# Serial-Enabled-LCD-Kit-v11.net
KiCad netlist of a schematic drawn in EAGLE
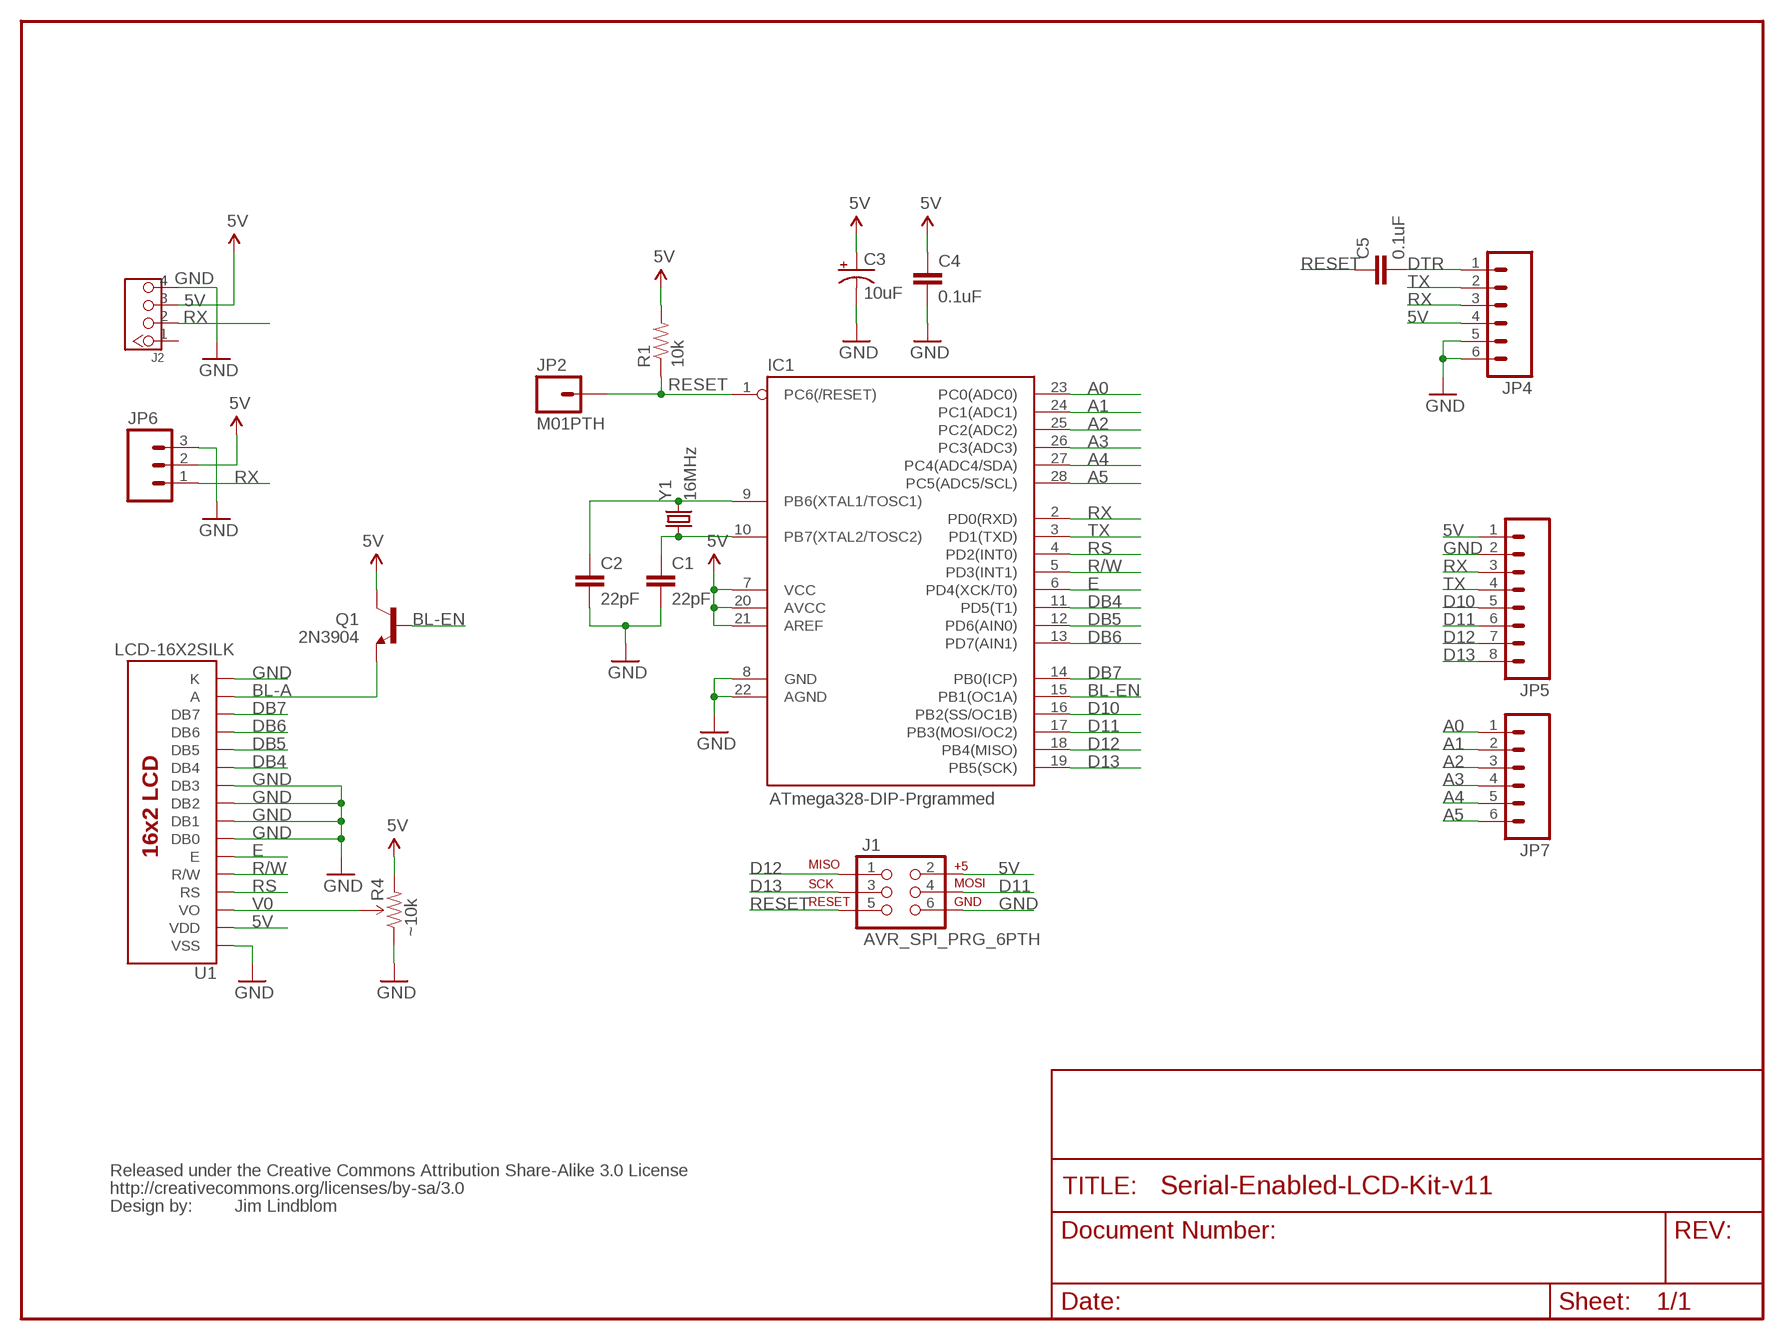
[diagram p0: schematic, sheet 1]

(export (version "E")
  (design (tool "Eeschema 10.0.6"))
  (components
    (comp (ref "C1")
      (value "22pF")
      (footprint "eagle-import:CAP-PTH-SMALL2")
      (libsource (lib "eagle-import") (part "CAPPTH2"))
    )
    (comp (ref "C2")
      (value "22pF")
      (footprint "eagle-import:CAP-PTH-SMALL2")
      (libsource (lib "eagle-import") (part "CAPPTH2"))
    )
    (comp (ref "C3")
      (value "10uF")
      (footprint "eagle-import:CPOL-RADIAL-10UF-25V")
      (libsource (lib "eagle-import") (part "CAP_POLPTH2"))
    )
    (comp (ref "C4")
      (value "0.1uF")
      (footprint "eagle-import:CAP-PTH-SMALL2")
      (libsource (lib "eagle-import") (part "CAPPTH2"))
    )
    (comp (ref "C5")
      (value "0.1uF")
      (footprint "eagle-import:CAP-PTH-SMALL2")
      (libsource (lib "eagle-import") (part "CAPPTH2"))
    )
    (comp (ref "IC1")
      (value "ATmega328-DIP-Prgrammed")
      (footprint "eagle-import:DIL28-3")
      (libsource (lib "eagle-import") (part "AVR-MEGA8-PPTH"))
    )
    (comp (ref "J1")
      (value "AVR_SPI_PRG_6PTH")
      (footprint "eagle-import:2X3")
      (libsource (lib "eagle-import") (part "AVR_SPI_PRG_6PTH"))
    )
    (comp (ref "J2")
      (value "TWIG-4P-2.0'90D'")
      (footprint "eagle-import:4P-2.0-90D")
      (libsource (lib "eagle-import") (part "TWIG-4P-2.0'90D'"))
    )
    (comp (ref "JP2")
      (value "M01PTH")
      (footprint "eagle-import:1X01")
      (libsource (lib "eagle-import") (part "M01PTH"))
    )
    (comp (ref "JP4")
      (value "M06SIP")
      (footprint "eagle-import:1X06")
      (libsource (lib "eagle-import") (part "M06SIP"))
    )
    (comp (ref "JP5")
      (value "M08")
      (footprint "eagle-import:1X08")
      (libsource (lib "eagle-import") (part "M08"))
    )
    (comp (ref "JP6")
      (value "M03PTH")
      (footprint "eagle-import:1X03")
      (libsource (lib "eagle-import") (part "M03PTH"))
    )
    (comp (ref "JP7")
      (value "M06SIP")
      (footprint "eagle-import:1X06")
      (libsource (lib "eagle-import") (part "M06SIP"))
    )
    (comp (ref "Q1")
      (value "2N3904")
      (footprint "eagle-import:TO-92")
      (libsource (lib "eagle-import") (part "TRANSISTOR_NPNTO92"))
    )
    (comp (ref "R1")
      (value "10k")
      (footprint "eagle-import:AXIAL-0.3")
      (libsource (lib "eagle-import") (part "RESISTORAXIAL-0.3"))
    )
    (comp (ref "R4")
      (value "~10k")
      (footprint "eagle-import:TRIM_POT_PTH")
      (libsource (lib "eagle-import") (part "TRIMPOTPTH"))
    )
    (comp (ref "U$4")
      (value "CREATIVE_COMMONS")
      (footprint "eagle-import:CREATIVE_COMMONS")
      (libsource (lib "eagle-import") (part "CREATIVE_COMMONS"))
    )
    (comp (ref "U1")
      (value "LCD-16X2SILK")
      (footprint "eagle-import:LCD-16X2")
      (libsource (lib "eagle-import") (part "LCD-16X2SILK"))
    )
    (comp (ref "Y1")
      (value "16MHz")
      (footprint "eagle-import:HC49US")
      (libsource (lib "eagle-import") (part "CRYSTALHC49US"))
    )
  )
  (nets
    (net (code "1") (name "/A0") (class "Default")
      (node (ref "IC1") (pin "23") (pinfunction "PC0(ADC0)_23") (pintype "bidirectional"))
      (node (ref "JP7") (pin "1") (pinfunction "1_1") (pintype "passive"))
    )
    (net (code "2") (name "/A1") (class "Default")
      (node (ref "IC1") (pin "24") (pinfunction "PC1(ADC1)_24") (pintype "bidirectional"))
      (node (ref "JP7") (pin "2") (pinfunction "2_2") (pintype "passive"))
    )
    (net (code "3") (name "/A2") (class "Default")
      (node (ref "IC1") (pin "25") (pinfunction "PC2(ADC2)_25") (pintype "bidirectional"))
      (node (ref "JP7") (pin "3") (pinfunction "3_3") (pintype "passive"))
    )
    (net (code "4") (name "/A3") (class "Default")
      (node (ref "IC1") (pin "26") (pinfunction "PC3(ADC3)_26") (pintype "bidirectional"))
      (node (ref "JP7") (pin "4") (pinfunction "4_4") (pintype "passive"))
    )
    (net (code "5") (name "/A4") (class "Default")
      (node (ref "IC1") (pin "27") (pinfunction "PC4(ADC4/SDA)_27") (pintype "bidirectional"))
      (node (ref "JP7") (pin "5") (pinfunction "5_5") (pintype "passive"))
    )
    (net (code "6") (name "/A5") (class "Default")
      (node (ref "IC1") (pin "28") (pinfunction "PC5(ADC5/SCL)_28") (pintype "bidirectional"))
      (node (ref "JP7") (pin "6") (pinfunction "6_6") (pintype "passive"))
    )
    (net (code "7") (name "/BL-A") (class "Default")
      (node (ref "Q1") (pin "1") (pinfunction "E_1") (pintype "passive"))
      (node (ref "U1") (pin "15") (pinfunction "A_15") (pintype "power_in"))
    )
    (net (code "8") (name "/BL-EN") (class "Default")
      (node (ref "IC1") (pin "15") (pinfunction "PB1(OC1A)_15") (pintype "bidirectional"))
      (node (ref "Q1") (pin "2") (pinfunction "B_2") (pintype "passive"))
    )
    (net (code "9") (name "/D10") (class "Default")
      (node (ref "IC1") (pin "16") (pinfunction "PB2(SS/OC1B)_16") (pintype "bidirectional"))
      (node (ref "JP5") (pin "5") (pinfunction "5_5") (pintype "passive"))
    )
    (net (code "10") (name "/D11") (class "Default")
      (node (ref "IC1") (pin "17") (pinfunction "PB3(MOSI/OC2)_17") (pintype "bidirectional"))
      (node (ref "J1") (pin "4") (pinfunction "4_4") (pintype "passive"))
      (node (ref "JP5") (pin "6") (pinfunction "6_6") (pintype "passive"))
    )
    (net (code "11") (name "/D12") (class "Default")
      (node (ref "IC1") (pin "18") (pinfunction "PB4(MISO)_18") (pintype "bidirectional"))
      (node (ref "J1") (pin "1") (pinfunction "1_1") (pintype "passive"))
      (node (ref "JP5") (pin "7") (pinfunction "7_7") (pintype "passive"))
    )
    (net (code "12") (name "/D13") (class "Default")
      (node (ref "IC1") (pin "19") (pinfunction "PB5(SCK)_19") (pintype "bidirectional"))
      (node (ref "J1") (pin "3") (pinfunction "3_3") (pintype "passive"))
      (node (ref "JP5") (pin "8") (pinfunction "8_8") (pintype "passive"))
    )
    (net (code "13") (name "/DB4") (class "Default")
      (node (ref "IC1") (pin "11") (pinfunction "PD5(T1)_11") (pintype "bidirectional"))
      (node (ref "U1") (pin "11") (pinfunction "DB4_11") (pintype "bidirectional"))
    )
    (net (code "14") (name "/DB5") (class "Default")
      (node (ref "IC1") (pin "12") (pinfunction "PD6(AIN0)_12") (pintype "bidirectional"))
      (node (ref "U1") (pin "12") (pinfunction "DB5_12") (pintype "bidirectional"))
    )
    (net (code "15") (name "/DB6") (class "Default")
      (node (ref "IC1") (pin "13") (pinfunction "PD7(AIN1)_13") (pintype "bidirectional"))
      (node (ref "U1") (pin "13") (pinfunction "DB6_13") (pintype "bidirectional"))
    )
    (net (code "16") (name "/DB7") (class "Default")
      (node (ref "IC1") (pin "14") (pinfunction "PB0(ICP)_14") (pintype "bidirectional"))
      (node (ref "U1") (pin "14") (pinfunction "DB7_14") (pintype "bidirectional"))
    )
    (net (code "17") (name "/DTR") (class "Default")
      (node (ref "C5") (pin "2") (pinfunction "2_2") (pintype "passive"))
      (node (ref "JP4") (pin "1") (pinfunction "1_1") (pintype "passive"))
    )
    (net (code "18") (name "/E") (class "Default")
      (node (ref "IC1") (pin "6") (pinfunction "PD4(XCK/T0)_6") (pintype "bidirectional"))
      (node (ref "U1") (pin "6") (pinfunction "E_6") (pintype "input"))
    )
    (net (code "19") (name "/RESET") (class "Default")
      (node (ref "C5") (pin "1") (pinfunction "1_1") (pintype "passive"))
      (node (ref "IC1") (pin "1") (pinfunction "PC6(/RESET)_1") (pintype "bidirectional"))
      (node (ref "J1") (pin "5") (pinfunction "5_5") (pintype "passive"))
      (node (ref "JP2") (pin "1") (pinfunction "1_1") (pintype "passive"))
      (node (ref "R1") (pin "P$1") (pinfunction "1_P$1") (pintype "passive"))
    )
    (net (code "20") (name "/RS") (class "Default")
      (node (ref "IC1") (pin "4") (pinfunction "PD2(INT0)_4") (pintype "bidirectional"))
      (node (ref "U1") (pin "4") (pinfunction "RS_4") (pintype "input"))
    )
    (net (code "21") (name "/RX") (class "Default")
      (node (ref "IC1") (pin "2") (pinfunction "PD0(RXD)_2") (pintype "bidirectional"))
      (node (ref "J2") (pin "2") (pinfunction "2_2") (pintype "bidirectional"))
      (node (ref "JP4") (pin "3") (pinfunction "3_3") (pintype "passive"))
      (node (ref "JP5") (pin "3") (pinfunction "3_3") (pintype "passive"))
      (node (ref "JP6") (pin "1") (pinfunction "1_1") (pintype "passive"))
    )
    (net (code "22") (name "/R{slash}W") (class "Default")
      (node (ref "IC1") (pin "5") (pinfunction "PD3(INT1)_5") (pintype "bidirectional"))
      (node (ref "U1") (pin "5") (pinfunction "R/W_5") (pintype "input"))
    )
    (net (code "23") (name "/TX") (class "Default")
      (node (ref "IC1") (pin "3") (pinfunction "PD1(TXD)_3") (pintype "bidirectional"))
      (node (ref "JP4") (pin "2") (pinfunction "2_2") (pintype "passive"))
      (node (ref "JP5") (pin "4") (pinfunction "4_4") (pintype "passive"))
    )
    (net (code "24") (name "/V0") (class "Default")
      (node (ref "R4") (pin "2") (pinfunction "WIPER_2") (pintype "passive"))
      (node (ref "U1") (pin "3") (pinfunction "VO_3") (pintype "bidirectional"))
    )
    (net (code "25") (name "5V") (class "Default")
      (node (ref "C3") (pin "1") (pinfunction "+_1") (pintype "passive"))
      (node (ref "C4") (pin "1") (pinfunction "1_1") (pintype "passive"))
      (node (ref "IC1") (pin "20") (pinfunction "AVCC_20") (pintype "bidirectional"))
      (node (ref "IC1") (pin "21") (pinfunction "AREF_21") (pintype "bidirectional"))
      (node (ref "IC1") (pin "7") (pinfunction "VCC_7") (pintype "bidirectional"))
      (node (ref "J1") (pin "2") (pinfunction "2_2") (pintype "passive"))
      (node (ref "J2") (pin "3") (pinfunction "3_3") (pintype "bidirectional"))
      (node (ref "JP4") (pin "4") (pinfunction "4_4") (pintype "passive"))
      (node (ref "JP5") (pin "1") (pinfunction "1_1") (pintype "passive"))
      (node (ref "JP6") (pin "2") (pinfunction "2_2") (pintype "passive"))
      (node (ref "Q1") (pin "3") (pinfunction "C_3") (pintype "passive"))
      (node (ref "R1") (pin "P$2") (pinfunction "2_P$2") (pintype "passive"))
      (node (ref "R4") (pin "3") (pinfunction "CW_3") (pintype "passive"))
      (node (ref "U1") (pin "2") (pinfunction "VDD_2") (pintype "power_in"))
    )
    (net (code "26") (name "GND") (class "Default")
      (node (ref "C1") (pin "2") (pinfunction "2_2") (pintype "passive"))
      (node (ref "C2") (pin "2") (pinfunction "2_2") (pintype "passive"))
      (node (ref "C3") (pin "2") (pinfunction "-_2") (pintype "passive"))
      (node (ref "C4") (pin "2") (pinfunction "2_2") (pintype "passive"))
      (node (ref "IC1") (pin "22") (pinfunction "AGND_22") (pintype "bidirectional"))
      (node (ref "IC1") (pin "8") (pinfunction "GND_8") (pintype "bidirectional"))
      (node (ref "J1") (pin "6") (pinfunction "6_6") (pintype "passive"))
      (node (ref "J2") (pin "4") (pinfunction "4_4") (pintype "bidirectional"))
      (node (ref "JP4") (pin "5") (pinfunction "5_5") (pintype "passive"))
      (node (ref "JP4") (pin "6") (pinfunction "6_6") (pintype "passive"))
      (node (ref "JP5") (pin "2") (pinfunction "2_2") (pintype "passive"))
      (node (ref "JP6") (pin "3") (pinfunction "3_3") (pintype "passive"))
      (node (ref "R4") (pin "1") (pinfunction "CCW_1") (pintype "passive"))
      (node (ref "U1") (pin "1") (pinfunction "VSS_1") (pintype "power_in"))
      (node (ref "U1") (pin "10") (pinfunction "DB3_10") (pintype "bidirectional"))
      (node (ref "U1") (pin "16") (pinfunction "K_16") (pintype "power_in"))
      (node (ref "U1") (pin "7") (pinfunction "DB0_7") (pintype "bidirectional"))
      (node (ref "U1") (pin "8") (pinfunction "DB1_8") (pintype "bidirectional"))
      (node (ref "U1") (pin "9") (pinfunction "DB2_9") (pintype "bidirectional"))
    )
    (net (code "27") (name "Net-(IC1-PB6(XTAL1{slash}TOSC1))") (class "Default")
      (node (ref "C2") (pin "1") (pinfunction "1_1") (pintype "passive"))
      (node (ref "IC1") (pin "9") (pinfunction "PB6(XTAL1/TOSC1)_9") (pintype "bidirectional"))
      (node (ref "Y1") (pin "2") (pinfunction "2_2") (pintype "passive"))
    )
    (net (code "28") (name "Net-(IC1-PB7(XTAL2{slash}TOSC2))") (class "Default")
      (node (ref "C1") (pin "1") (pinfunction "1_1") (pintype "passive"))
      (node (ref "IC1") (pin "10") (pinfunction "PB7(XTAL2/TOSC2)_10") (pintype "bidirectional"))
      (node (ref "Y1") (pin "1") (pinfunction "1_1") (pintype "passive"))
    )
    (net (code "29") (name "unconnected-(J2-Pad1)") (class "Default")
      (node (ref "J2") (pin "1") (pinfunction "1_1") (pintype "bidirectional"))
    )
  )
)
